# DUAL_OUT_LEDs.net
KiCad netlist of a schematic drawn in EAGLE
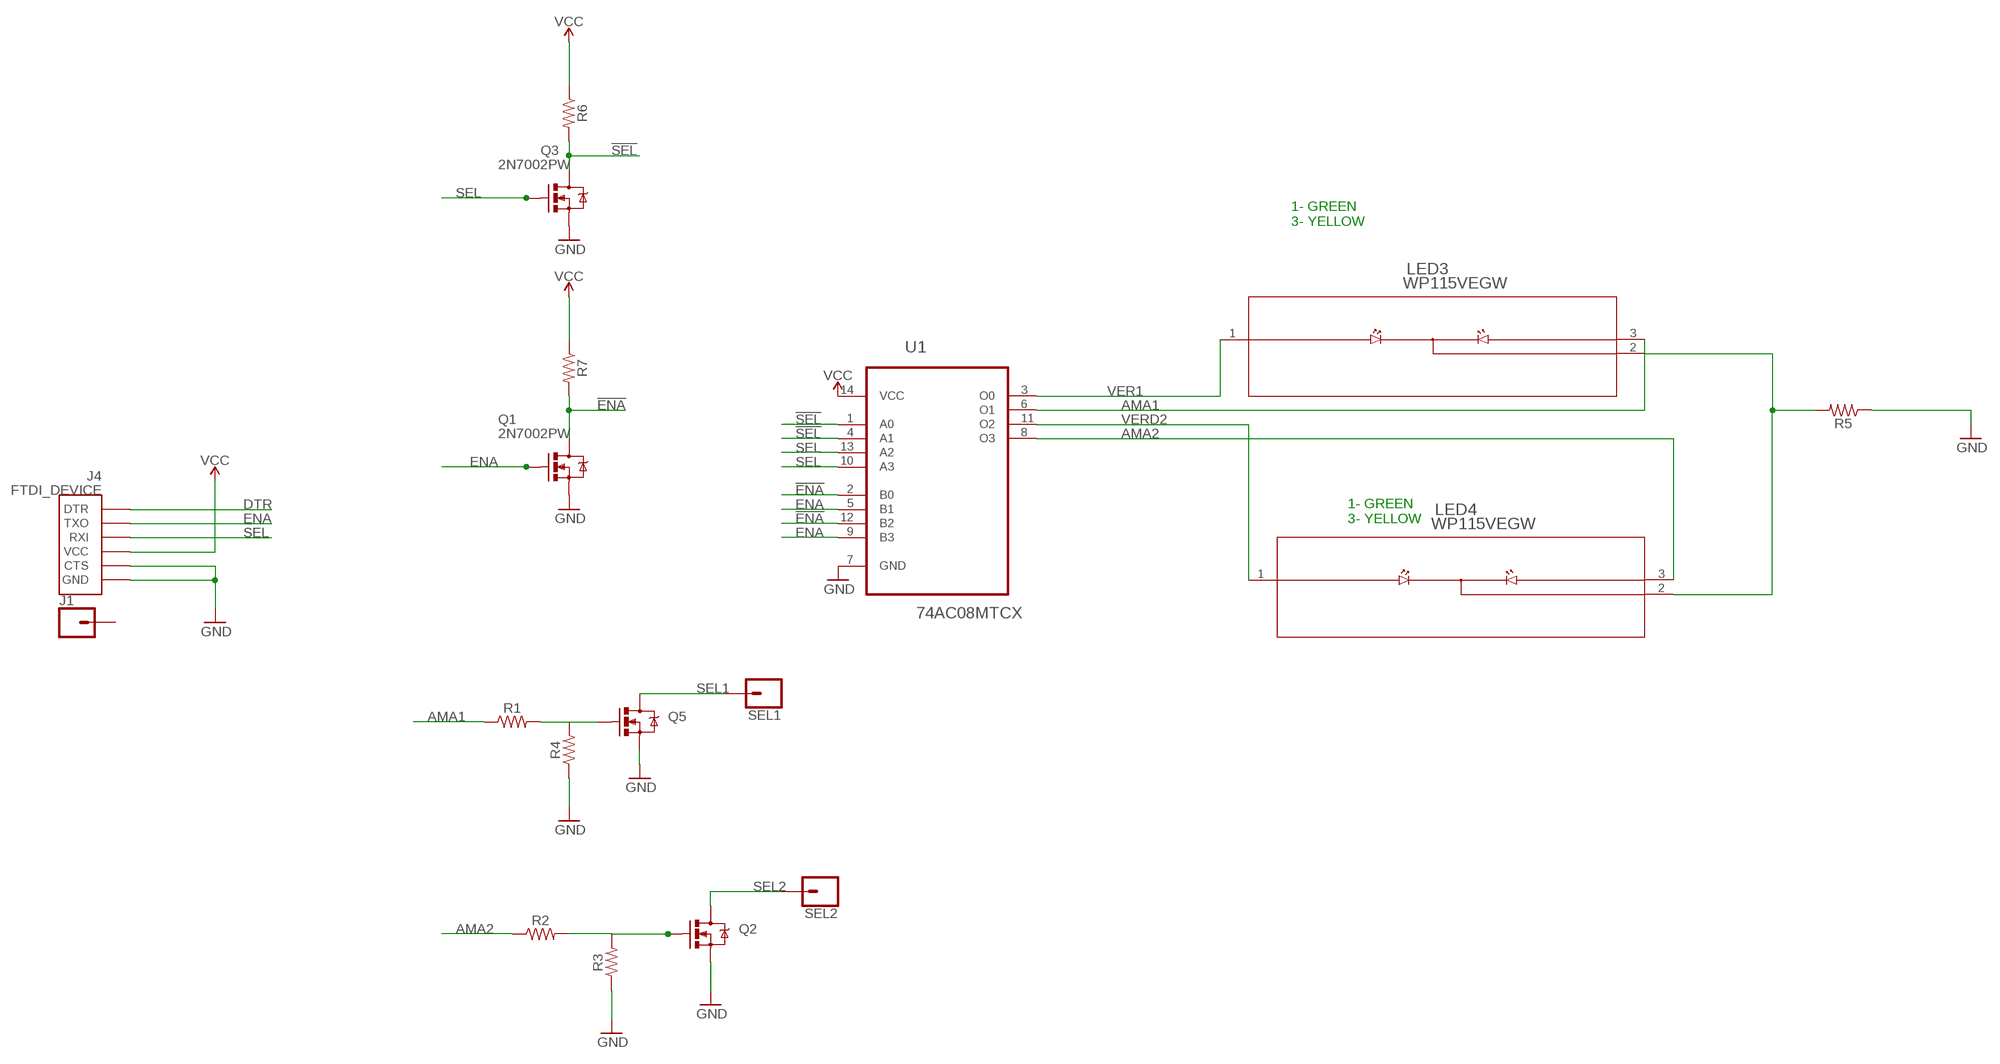
[diagram p0: schematic, sheet 1, part 1 of 2]
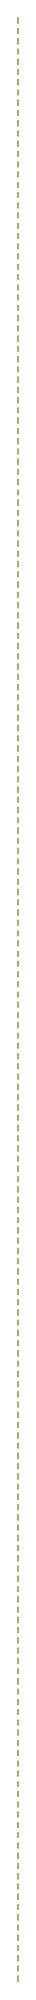
[diagram p1: schematic, sheet 1, part 2 of 2]

(export (version "E")
  (design (tool "Eeschema 10.0.6"))
  (components
    (comp (ref "J1")
      (value "CONN_01")
      (footprint "eagle-import:1X01")
      (libsource (lib "eagle-import") (part "CONN_01"))
    )
    (comp (ref "J4")
      (value "FTDI_DEVICE")
      (footprint "eagle-import:FTDI_DEVICE_SIDE")
      (libsource (lib "eagle-import") (part "FTDI_DEVICE"))
    )
    (comp (ref "LED3")
      (value "WP115VEGW")
      (footprint "eagle-import:WP115VEGW_KNB")
      (fields (field (name "COPYRIGHT") "Copyright (C) 2018 Accelerated Designs. All rights reserved"))
      (libsource (lib "eagle-import") (part "WP115VEGW"))
    )
    (comp (ref "LED4")
      (value "WP115VEGW")
      (footprint "eagle-import:WP115VEGW_KNB")
      (fields (field (name "COPYRIGHT") "Copyright (C) 2018 Accelerated Designs. All rights reserved"))
      (libsource (lib "eagle-import") (part "WP115VEGW"))
    )
    (comp (ref "Q1")
      (value "2N7002PW")
      (footprint "eagle-import:SOT323")
      (libsource (lib "eagle-import") (part "MOSFET-NCHANNEL2N7002PW"))
    )
    (comp (ref "Q2")
      (value "2N7002PW")
      (footprint "eagle-import:SOT323")
      (libsource (lib "eagle-import") (part "MOSFET-NCHANNEL2N7002PW"))
    )
    (comp (ref "Q3")
      (value "2N7002PW")
      (footprint "eagle-import:SOT323")
      (libsource (lib "eagle-import") (part "MOSFET-NCHANNEL2N7002PW"))
    )
    (comp (ref "Q5")
      (value "2N7002PW")
      (footprint "eagle-import:SOT323")
      (libsource (lib "eagle-import") (part "MOSFET-NCHANNEL2N7002PW"))
    )
    (comp (ref "R1")
      (value "RESISTOR0805")
      (footprint "eagle-import:0805")
      (libsource (lib "eagle-import") (part "RESISTOR0805"))
    )
    (comp (ref "R2")
      (value "RESISTOR0805")
      (footprint "eagle-import:0805")
      (libsource (lib "eagle-import") (part "RESISTOR0805"))
    )
    (comp (ref "R3")
      (value "RESISTOR0805")
      (footprint "eagle-import:0805")
      (libsource (lib "eagle-import") (part "RESISTOR0805"))
    )
    (comp (ref "R4")
      (value "RESISTOR0805")
      (footprint "eagle-import:0805")
      (libsource (lib "eagle-import") (part "RESISTOR0805"))
    )
    (comp (ref "R5")
      (value "RESISTOR0805")
      (footprint "eagle-import:0805")
      (libsource (lib "eagle-import") (part "RESISTOR0805"))
    )
    (comp (ref "R6")
      (value "RESISTOR0805")
      (footprint "eagle-import:0805")
      (libsource (lib "eagle-import") (part "RESISTOR0805"))
    )
    (comp (ref "R7")
      (value "RESISTOR0805")
      (footprint "eagle-import:0805")
      (libsource (lib "eagle-import") (part "RESISTOR0805"))
    )
    (comp (ref "SEL1")
      (value "CONN_01")
      (footprint "eagle-import:1X01")
      (libsource (lib "eagle-import") (part "CONN_01"))
    )
    (comp (ref "SEL2")
      (value "CONN_01")
      (footprint "eagle-import:1X01")
      (libsource (lib "eagle-import") (part "CONN_01"))
    )
    (comp (ref "U1")
      (value "74AC08MTCX")
      (footprint "eagle-import:SOP65P640X120-14N")
      (fields (field (name "MF") "ON"))
      (libsource (lib "eagle-import") (part "74AC08MTCX"))
    )
  )
  (nets
    (net (code "1") (name "/AMA1") (class "Default")
      (node (ref "LED3") (pin "3") (pinfunction "3_3") (pintype "passive"))
      (node (ref "R1") (pin "1") (pinfunction "1_1") (pintype "passive"))
      (node (ref "U1") (pin "6") (pinfunction "O1_6") (pintype "output"))
    )
    (net (code "2") (name "/AMA2") (class "Default")
      (node (ref "LED4") (pin "3") (pinfunction "3_3") (pintype "passive"))
      (node (ref "R2") (pin "1") (pinfunction "1_1") (pintype "passive"))
      (node (ref "U1") (pin "8") (pinfunction "O3_8") (pintype "output"))
    )
    (net (code "3") (name "/DTR") (class "Default")
      (node (ref "J4") (pin "P$1") (pinfunction "DTR_P$1") (pintype "bidirectional"))
    )
    (net (code "4") (name "/ENA") (class "Default")
      (node (ref "J4") (pin "P$2") (pinfunction "TXO_P$2") (pintype "bidirectional"))
      (node (ref "Q1") (pin "1") (pinfunction "G_1") (pintype "passive"))
      (node (ref "U1") (pin "5") (pinfunction "B1_5") (pintype "input"))
      (node (ref "U1") (pin "9") (pinfunction "B3_9") (pintype "input"))
    )
    (net (code "5") (name "/SEL") (class "Default")
      (node (ref "J4") (pin "P$3") (pinfunction "RXI_P$3") (pintype "bidirectional"))
      (node (ref "Q3") (pin "1") (pinfunction "G_1") (pintype "passive"))
      (node (ref "U1") (pin "10") (pinfunction "A3_10") (pintype "input"))
      (node (ref "U1") (pin "13") (pinfunction "A2_13") (pintype "input"))
    )
    (net (code "6") (name "/SEL1") (class "Default")
      (node (ref "Q5") (pin "3") (pinfunction "D_3") (pintype "passive"))
      (node (ref "SEL1") (pin "1") (pinfunction "1_1") (pintype "passive"))
    )
    (net (code "7") (name "/SEL2") (class "Default")
      (node (ref "Q2") (pin "3") (pinfunction "D_3") (pintype "passive"))
      (node (ref "SEL2") (pin "1") (pinfunction "1_1") (pintype "passive"))
    )
    (net (code "8") (name "/VER1") (class "Default")
      (node (ref "LED3") (pin "1") (pinfunction "1_1") (pintype "passive"))
      (node (ref "U1") (pin "3") (pinfunction "O0_3") (pintype "output"))
    )
    (net (code "9") (name "/VERD2") (class "Default")
      (node (ref "LED4") (pin "1") (pinfunction "1_1") (pintype "passive"))
      (node (ref "U1") (pin "11") (pinfunction "O2_11") (pintype "output"))
    )
    (net (code "10") (name "/~{ENA}") (class "Default")
      (node (ref "Q1") (pin "3") (pinfunction "D_3") (pintype "passive"))
      (node (ref "R7") (pin "2") (pinfunction "2_2") (pintype "passive"))
      (node (ref "U1") (pin "12") (pinfunction "B2_12") (pintype "input"))
      (node (ref "U1") (pin "2") (pinfunction "B0_2") (pintype "input"))
    )
    (net (code "11") (name "/~{SEL}") (class "Default")
      (node (ref "Q3") (pin "3") (pinfunction "D_3") (pintype "passive"))
      (node (ref "R6") (pin "2") (pinfunction "2_2") (pintype "passive"))
      (node (ref "U1") (pin "1") (pinfunction "A0_1") (pintype "input"))
      (node (ref "U1") (pin "4") (pinfunction "A1_4") (pintype "input"))
    )
    (net (code "12") (name "GND") (class "Default")
      (node (ref "J4") (pin "P$5") (pinfunction "CTS_P$5") (pintype "bidirectional"))
      (node (ref "J4") (pin "P$6") (pinfunction "GND_P$6") (pintype "bidirectional"))
      (node (ref "Q1") (pin "2") (pinfunction "S_2") (pintype "passive"))
      (node (ref "Q2") (pin "2") (pinfunction "S_2") (pintype "passive"))
      (node (ref "Q3") (pin "2") (pinfunction "S_2") (pintype "passive"))
      (node (ref "Q5") (pin "2") (pinfunction "S_2") (pintype "passive"))
      (node (ref "R3") (pin "1") (pinfunction "1_1") (pintype "passive"))
      (node (ref "R4") (pin "1") (pinfunction "1_1") (pintype "passive"))
      (node (ref "R5") (pin "1") (pinfunction "1_1") (pintype "passive"))
      (node (ref "U1") (pin "7") (pinfunction "GND_7") (pintype "passive"))
    )
    (net (code "13") (name "Net-(LED3-Pad2)") (class "Default")
      (node (ref "LED3") (pin "2") (pinfunction "2_2") (pintype "passive"))
      (node (ref "LED4") (pin "2") (pinfunction "2_2") (pintype "passive"))
      (node (ref "R5") (pin "2") (pinfunction "2_2") (pintype "passive"))
    )
    (net (code "14") (name "Net-(Q2-G)") (class "Default")
      (node (ref "Q2") (pin "1") (pinfunction "G_1") (pintype "passive"))
      (node (ref "R2") (pin "2") (pinfunction "2_2") (pintype "passive"))
      (node (ref "R3") (pin "2") (pinfunction "2_2") (pintype "passive"))
    )
    (net (code "15") (name "Net-(Q5-G)") (class "Default")
      (node (ref "Q5") (pin "1") (pinfunction "G_1") (pintype "passive"))
      (node (ref "R1") (pin "2") (pinfunction "2_2") (pintype "passive"))
      (node (ref "R4") (pin "2") (pinfunction "2_2") (pintype "passive"))
    )
    (net (code "16") (name "VCC") (class "Default")
      (node (ref "J4") (pin "P$4") (pinfunction "VCC_P$4") (pintype "bidirectional"))
      (node (ref "R6") (pin "1") (pinfunction "1_1") (pintype "passive"))
      (node (ref "R7") (pin "1") (pinfunction "1_1") (pintype "passive"))
      (node (ref "U1") (pin "14") (pinfunction "VCC_14") (pintype "power_in"))
    )
    (net (code "17") (name "unconnected-(J1-Pad1)") (class "Default")
      (node (ref "J1") (pin "1") (pinfunction "1_1") (pintype "passive"))
    )
  )
)
